# SwitchIntegration.net
KiCad netlist of a schematic drawn in Altium Designer
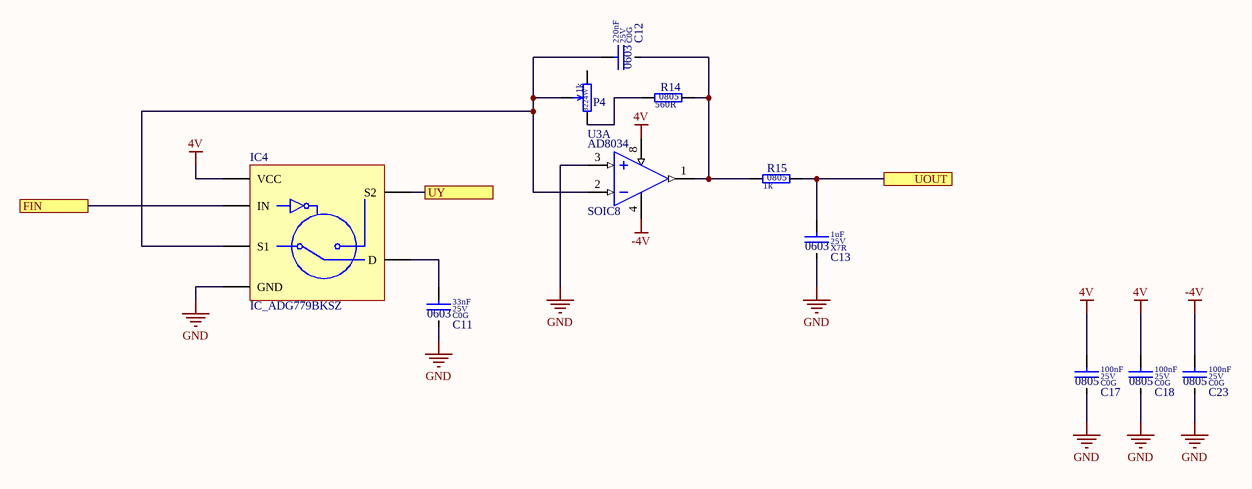
[diagram p0: SwitchIntegration.SchDoc]

(export (version "E")
  (design (tool "Eeschema 10.0.6"))
  (components
    (comp (ref "C11")
      (value "33nF")
      (footprint "C_0603_1608")
      (description "Capacitor")
      (fields
        (field (name "DIELECTRIC") "C0G")
        (field (name "VOLTAGE") "25V")
        (field (name "SCH_FOOTPRINT") "0603")
        (field (name "Comment") "C_33nF_0603_C0G_25V_5")
      )
      (libsource (lib "SIUE_Symbol") (part "C_33nF_0603_C0G_25V_5"))
    )
    (comp (ref "C12")
      (value "220nF")
      (footprint "C_0603_1608")
      (description "Capacitor")
      (fields
        (field (name "DIELECTRIC") "C0G")
        (field (name "VOLTAGE") "25V")
        (field (name "SCH_FOOTPRINT") "0603")
        (field (name "Comment") "C_220nF_0603_C0G_25V_5")
      )
      (libsource (lib "SIUE_Symbol") (part "C_220nF_0603_C0G_25V_5"))
    )
    (comp (ref "C13")
      (value "1uF")
      (footprint "C_1206_3216")
      (description "Capacitor")
      (fields
        (field (name "DIELECTRIC") "X7R")
        (field (name "VOLTAGE") "25V")
        (field (name "SCH_FOOTPRINT") "0603")
        (field (name "Comment") "C_1uF_1206_X7R_25V_5")
      )
      (libsource (lib "SIUE_Symbol") (part "C_1uF_1206_X7R_25V_5"))
    )
    (comp (ref "C17")
      (value "100nF")
      (footprint "C_0805_2012")
      (description "Capacitor")
      (fields
        (field (name "DIELECTRIC") "C0G")
        (field (name "VOLTAGE") "25V")
        (field (name "SCH_FOOTPRINT") "0805")
        (field (name "Comment") "C_100nF_0805_C0G_25V_5")
      )
      (libsource (lib "SIUE_Symbol") (part "C_100nF_0805_C0G_25V_5"))
    )
    (comp (ref "C18")
      (value "100nF")
      (footprint "C_0805_2012")
      (description "Capacitor")
      (fields
        (field (name "DIELECTRIC") "C0G")
        (field (name "VOLTAGE") "25V")
        (field (name "SCH_FOOTPRINT") "0805")
        (field (name "Comment") "C_100nF_0805_C0G_25V_5")
      )
      (libsource (lib "SIUE_Symbol") (part "C_100nF_0805_C0G_25V_5"))
    )
    (comp (ref "C23")
      (value "100nF")
      (footprint "C_0805_2012")
      (description "Capacitor")
      (fields
        (field (name "DIELECTRIC") "C0G")
        (field (name "VOLTAGE") "25V")
        (field (name "SCH_FOOTPRINT") "0805")
        (field (name "Comment") "C_100nF_0805_C0G_25V_5")
      )
      (libsource (lib "SIUE_Symbol") (part "C_100nF_0805_C0G_25V_5"))
    )
    (comp (ref "IC4")
      (value "IC_ADG779BKSZ")
      (footprint "SC70")
      (libsource (lib "SIUE_Symbol") (part "IC_ADG779BKSZ"))
    )
    (comp (ref "P4")
      (value "1k")
      (footprint "Potentiometer")
      (fields (field (name "SCH_FOOTPRINT") "3224W") (field (name "Comment") "POT_1k"))
      (libsource (lib "SIUE_Symbol") (part "POT_1k"))
    )
    (comp (ref "R14")
      (value "R_560R_0805_5")
      (footprint "R_0805_2012")
      (fields
        (field (name "TOLERANCE") "5")
        (field (name "SCH_FOOTPRINT") "0805")
        (field (name "RESISTANCE") "560R")
      )
      (libsource (lib "SIUE_Symbol") (part "R_560R_0805_5"))
    )
    (comp (ref "R15")
      (value "R_1k_0805_5")
      (footprint "R_0805_2012")
      (fields
        (field (name "TOLERANCE") "5")
        (field (name "SCH_FOOTPRINT") "0805")
        (field (name "RESISTANCE") "1k")
      )
      (libsource (lib "SIUE_Symbol") (part "R_1k_0805_5"))
    )
    (comp (ref "U3")
      (value "AD8034")
      (footprint "SO8")
      (fields (field (name "SCH_FOOTPRINT") "SOIC8") (field (name "Comment") "A2_AD8034"))
      (libsource (lib "SIUE_Symbol") (part "A2_AD8034"))
    )
  )
  (nets
    (net (code "1") (name "-4V") (class "Default")
      (node (ref "C23") (pin "1") (pinfunction "1_1") (pintype "passive"))
      (node (ref "U3") (pin "4") (pinfunction "GND_4") (pintype "power_in"))
    )
    (net (code "2") (name "/FIN") (class "Default")
      (node (ref "IC4") (pin "1") (pinfunction "IN_1") (pintype "passive"))
    )
    (net (code "3") (name "/UOUT") (class "Default")
      (node (ref "C13") (pin "1") (pinfunction "1_1") (pintype "passive"))
      (node (ref "R15") (pin "2") (pinfunction "2_2") (pintype "passive"))
    )
    (net (code "4") (name "/UY") (class "Default")
      (node (ref "IC4") (pin "6") (pinfunction "S2_6") (pintype "passive"))
    )
    (net (code "5") (name "4V") (class "Default")
      (node (ref "C17") (pin "1") (pinfunction "1_1") (pintype "passive"))
      (node (ref "C18") (pin "1") (pinfunction "1_1") (pintype "passive"))
      (node (ref "IC4") (pin "2") (pinfunction "VCC_2") (pintype "passive"))
      (node (ref "U3") (pin "8") (pinfunction "VDD_8") (pintype "input"))
    )
    (net (code "6") (name "GND") (class "Default")
      (node (ref "C11") (pin "2") (pinfunction "2_2") (pintype "passive"))
      (node (ref "C13") (pin "2") (pinfunction "2_2") (pintype "passive"))
      (node (ref "C17") (pin "2") (pinfunction "2_2") (pintype "passive"))
      (node (ref "C18") (pin "2") (pinfunction "2_2") (pintype "passive"))
      (node (ref "C23") (pin "2") (pinfunction "2_2") (pintype "passive"))
      (node (ref "IC4") (pin "3") (pinfunction "GND_3") (pintype "passive"))
      (node (ref "U3") (pin "3") (pinfunction "IN+1_3") (pintype "input"))
    )
    (net (code "7") (name "Net-(IC4-D)") (class "Default")
      (node (ref "C11") (pin "1") (pinfunction "1_1") (pintype "passive"))
      (node (ref "IC4") (pin "5") (pinfunction "D_5") (pintype "passive"))
    )
    (net (code "8") (name "Net-(IC4-S1)") (class "Default")
      (node (ref "C12") (pin "1") (pinfunction "1_1") (pintype "passive"))
      (node (ref "IC4") (pin "4") (pinfunction "S1_4") (pintype "passive"))
      (node (ref "P4") (pin "2") (pinfunction "2_2") (pintype "passive"))
      (node (ref "U3") (pin "2") (pinfunction "IN-1_2") (pintype "input"))
    )
    (net (code "9") (name "Net-(P4-Pad3)") (class "Default")
      (node (ref "P4") (pin "3") (pinfunction "3_3") (pintype "passive"))
      (node (ref "R14") (pin "1") (pinfunction "1_1") (pintype "passive"))
    )
    (net (code "10") (name "Net-(U3A-OUT1)") (class "Default")
      (node (ref "C12") (pin "2") (pinfunction "2_2") (pintype "passive"))
      (node (ref "R14") (pin "2") (pinfunction "2_2") (pintype "passive"))
      (node (ref "R15") (pin "1") (pinfunction "1_1") (pintype "passive"))
      (node (ref "U3") (pin "1") (pinfunction "OUT1_1") (pintype "output"))
    )
    (net (code "11") (name "unconnected-(P4-Pad1)") (class "Default")
      (node (ref "P4") (pin "1") (pinfunction "1_1") (pintype "passive"))
    )
  )
)
